# FPGA-Misc.net
KiCad netlist of a schematic drawn in Altium Designer
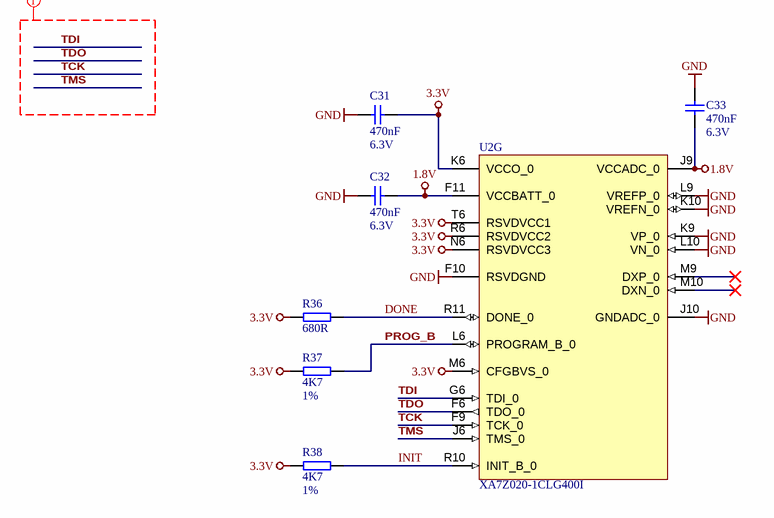
[diagram p0: FPGA-Misc.SchDoc]

(export (version "E")
  (design (tool "Eeschema 10.0.6"))
  (components
    (comp (ref "C31")
      (value "470nF")
      (footprint "CAPC0603X33N")
      (description "KON 470nF X5R 6.3V SMD")
      (fields (field (name "VOLTAGE") "6.3V") (field (name "TOLERANCE") "20%"))
      (libsource (lib "TE") (part "CAP-NP"))
    )
    (comp (ref "C32")
      (value "470nF")
      (footprint "CAPC0603X33N")
      (description "KON 470nF X5R 6.3V SMD")
      (fields (field (name "VOLTAGE") "6.3V") (field (name "TOLERANCE") "20%"))
      (libsource (lib "TE") (part "CAP-NP"))
    )
    (comp (ref "C33")
      (value "470nF")
      (footprint "CAPC0603X33N")
      (description "KON 470nF X5R 6.3V SMD")
      (fields (field (name "VOLTAGE") "6.3V") (field (name "TOLERANCE") "20%"))
      (libsource (lib "TE") (part "CAP-NP"))
    )
    (comp (ref "R36")
      (value "680R")
      (footprint "RESC1005X40N")
      (description "WID SMD 680R 1% 0,063W")
      (libsource (lib "TE") (part "RES"))
    )
    (comp (ref "R37")
      (value "4K7")
      (footprint "RESC0603X26N")
      (description "WID SMD 4K7 1% 0,05W")
      (fields (field (name "TOLERANCE") "1%"))
      (libsource (lib "TE") (part "RES"))
    )
    (comp (ref "R38")
      (value "4K7")
      (footprint "RESC0603X26N")
      (description "WID SMD 4K7 1% 0,05W")
      (fields (field (name "TOLERANCE") "1%"))
      (libsource (lib "TE") (part "RES"))
    )
    (comp (ref "U2")
      (value "XA7Z020-1CLG400I")
      (footprint "BGA400C80P20X20_1700X1700X160N")
      (libsource (lib "TE") (part "XC7Z020-2CLG400C"))
    )
  )
  (nets
    (net (code "1") (name "/DONE") (class "Default")
      (node (ref "R36") (pin "2") (pinfunction "2_2") (pintype "passive"))
      (node (ref "U2") (pin "R11") (pinfunction "DONE_0_R11") (pintype "bidirectional"))
    )
    (net (code "2") (name "/INIT") (class "Default")
      (node (ref "R38") (pin "1") (pinfunction "1_1") (pintype "passive"))
      (node (ref "U2") (pin "R10") (pinfunction "INIT_B_0_R10") (pintype "input"))
    )
    (net (code "3") (name "/PROG_B") (class "Default")
      (node (ref "R37") (pin "1") (pinfunction "1_1") (pintype "passive"))
      (node (ref "U2") (pin "L6") (pinfunction "PROGRAM_B_0_L6") (pintype "bidirectional"))
    )
    (net (code "4") (name "/TCK") (class "Default")
      (node (ref "U2") (pin "F9") (pinfunction "TCK_0_F9") (pintype "input"))
    )
    (net (code "5") (name "/TDI") (class "Default")
      (node (ref "U2") (pin "G6") (pinfunction "TDI_0_G6") (pintype "input"))
    )
    (net (code "6") (name "/TDO") (class "Default")
      (node (ref "U2") (pin "F6") (pinfunction "TDO_0_F6") (pintype "output"))
    )
    (net (code "7") (name "/TMS") (class "Default")
      (node (ref "U2") (pin "J6") (pinfunction "TMS_0_J6") (pintype "input"))
    )
    (net (code "8") (name "1.8V") (class "Default")
      (node (ref "C32") (pin "2") (pinfunction "2_2") (pintype "passive"))
      (node (ref "C33") (pin "2") (pinfunction "2_2") (pintype "passive"))
      (node (ref "U2") (pin "F11") (pinfunction "VCCBATT_0_F11") (pintype "power_in"))
      (node (ref "U2") (pin "J9") (pinfunction "VCCADC_0_J9") (pintype "power_in"))
    )
    (net (code "9") (name "3.3V") (class "Default")
      (node (ref "C31") (pin "2") (pinfunction "2_2") (pintype "passive"))
      (node (ref "R36") (pin "1") (pinfunction "1_1") (pintype "passive"))
      (node (ref "R37") (pin "2") (pinfunction "2_2") (pintype "passive"))
      (node (ref "R38") (pin "2") (pinfunction "2_2") (pintype "passive"))
      (node (ref "U2") (pin "K6") (pinfunction "VCCO_0_K6") (pintype "power_in"))
      (node (ref "U2") (pin "M6") (pinfunction "CFGBVS_0_M6") (pintype "input"))
      (node (ref "U2") (pin "N6") (pinfunction "RSVDVCC3_N6") (pintype "power_in"))
      (node (ref "U2") (pin "R6") (pinfunction "RSVDVCC2_R6") (pintype "power_in"))
      (node (ref "U2") (pin "T6") (pinfunction "RSVDVCC1_T6") (pintype "power_in"))
    )
    (net (code "10") (name "GND") (class "Default")
      (node (ref "C31") (pin "1") (pinfunction "1_1") (pintype "passive"))
      (node (ref "C32") (pin "1") (pinfunction "1_1") (pintype "passive"))
      (node (ref "C33") (pin "1") (pinfunction "1_1") (pintype "passive"))
      (node (ref "U2") (pin "F10") (pinfunction "RSVDGND_F10") (pintype "power_in"))
      (node (ref "U2") (pin "J10") (pinfunction "GNDADC_0_J10") (pintype "power_in"))
      (node (ref "U2") (pin "K10") (pinfunction "VREFN_0_K10") (pintype "bidirectional"))
      (node (ref "U2") (pin "K9") (pinfunction "VP_0_K9") (pintype "input"))
      (node (ref "U2") (pin "L10") (pinfunction "VN_0_L10") (pintype "input"))
      (node (ref "U2") (pin "L9") (pinfunction "VREFP_0_L9") (pintype "bidirectional"))
    )
    (net (code "11") (name "unconnected-(U2G-DXN_0-PadM10)") (class "Default")
      (node (ref "U2") (pin "M10") (pinfunction "DXN_0_M10") (pintype "input+no_connect"))
    )
    (net (code "12") (name "unconnected-(U2G-DXP_0-PadM9)") (class "Default")
      (node (ref "U2") (pin "M9") (pinfunction "DXP_0_M9") (pintype "input+no_connect"))
    )
  )
)
